# LED_driver.net
KiCad netlist of a schematic drawn in EAGLE
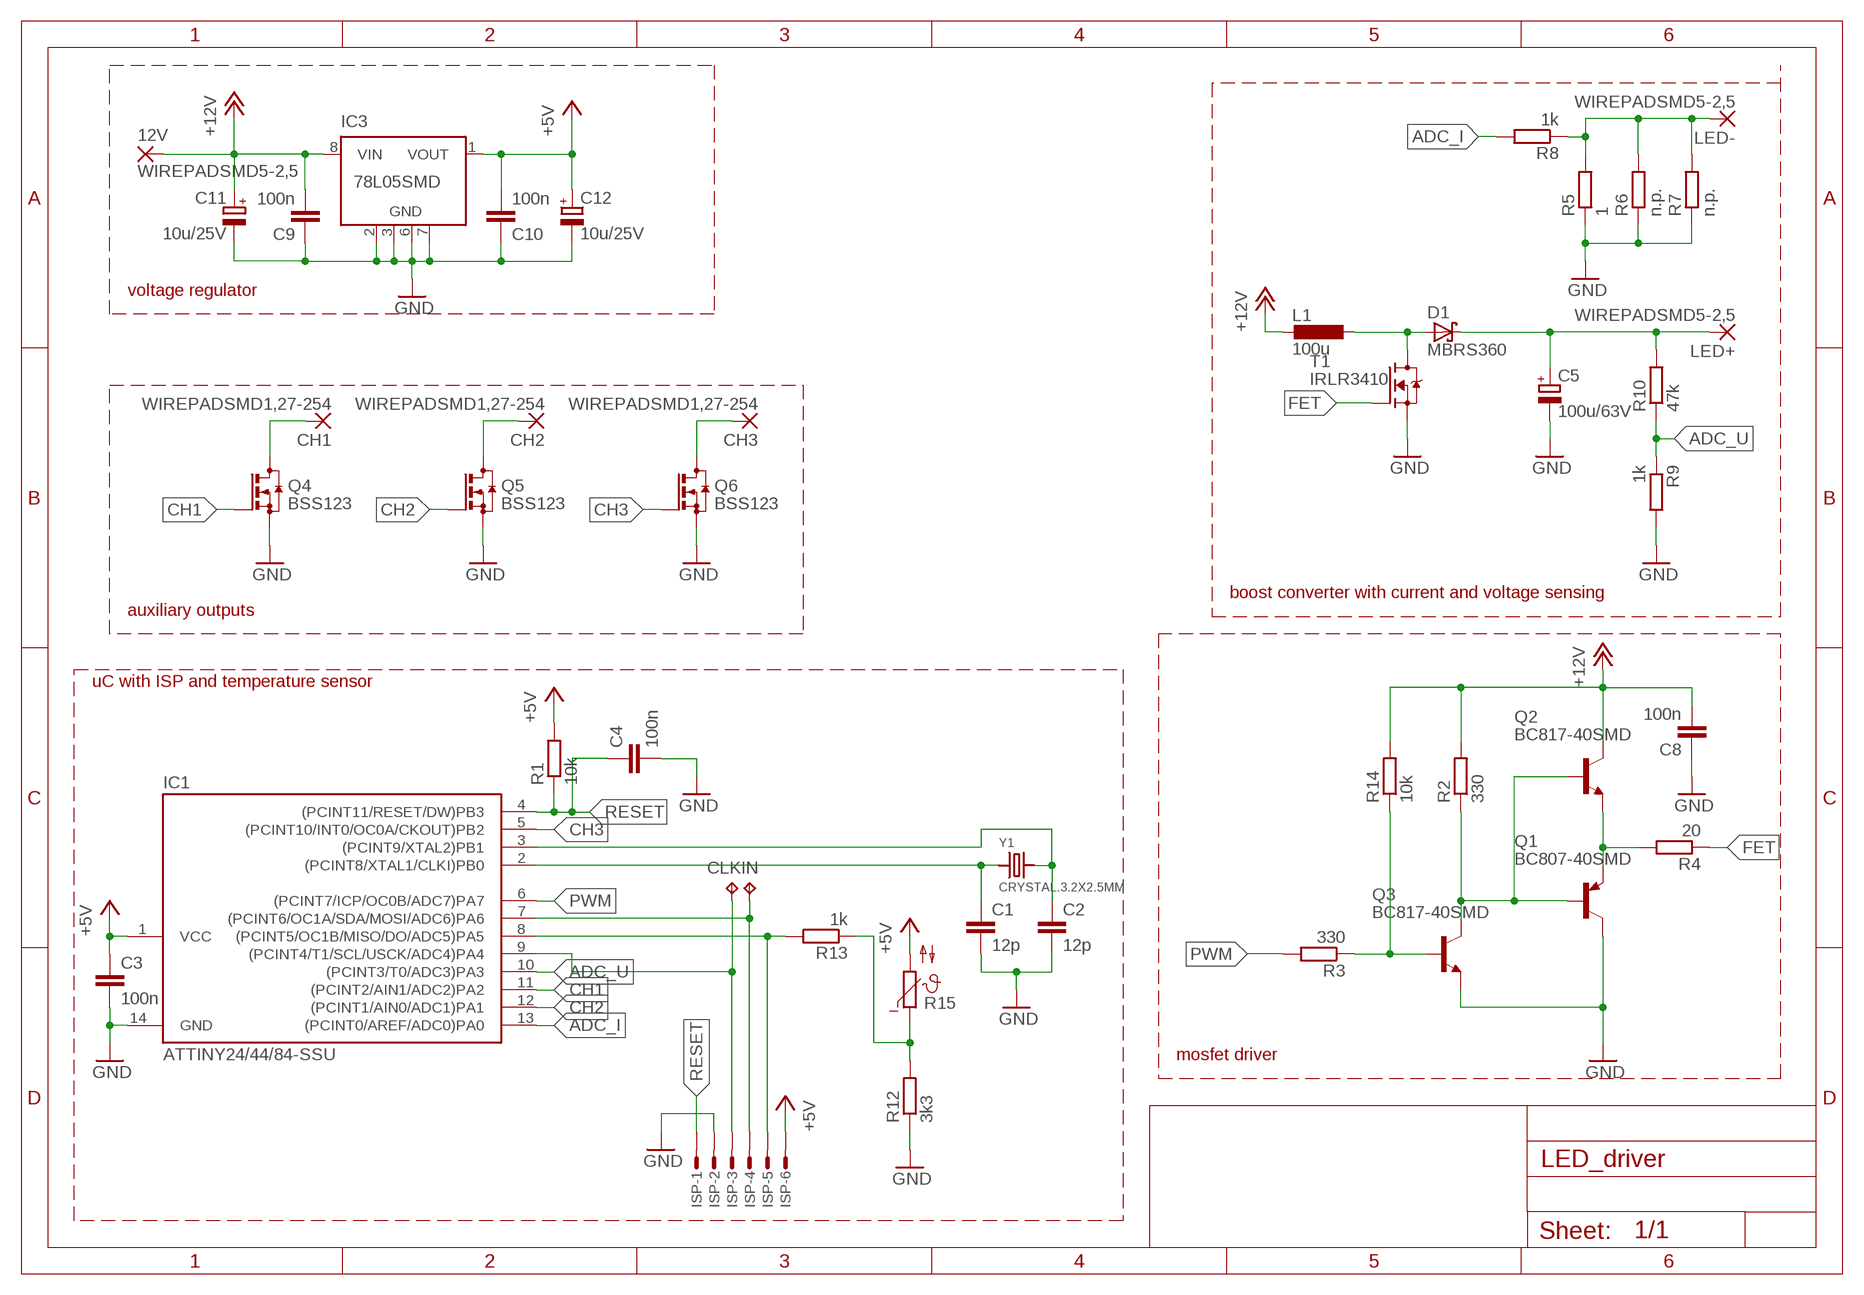
[diagram p0: schematic, sheet 1]

(export (version "E")
  (design (tool "Eeschema 10.0.6"))
  (components
    (comp (ref "12V")
      (value "WIREPADSMD5-2,5")
      (footprint "eagle-import:5-2,5")
      (libsource (lib "eagle-import") (part "WIREPADSMD5-2,5"))
    )
    (comp (ref "C1")
      (value "12p")
      (footprint "eagle-import:C0603K")
      (libsource (lib "eagle-import") (part "C-EUC0603K"))
    )
    (comp (ref "C2")
      (value "12p")
      (footprint "eagle-import:C0603K")
      (libsource (lib "eagle-import") (part "C-EUC0603K"))
    )
    (comp (ref "C3")
      (value "100n")
      (footprint "eagle-import:C0603K")
      (libsource (lib "eagle-import") (part "C-EUC0603K"))
    )
    (comp (ref "C4")
      (value "100n")
      (footprint "eagle-import:C0603K")
      (libsource (lib "eagle-import") (part "C-EUC0603K"))
    )
    (comp (ref "C5")
      (value "100u/63V")
      (footprint "eagle-import:153CLV-1010")
      (libsource (lib "eagle-import") (part "CPOL-EU153CLV-1010"))
    )
    (comp (ref "C8")
      (value "100n")
      (footprint "eagle-import:C0603K")
      (libsource (lib "eagle-import") (part "C-EUC0603K"))
    )
    (comp (ref "C9")
      (value "100n")
      (footprint "eagle-import:C0603K")
      (libsource (lib "eagle-import") (part "C-EUC0603K"))
    )
    (comp (ref "C10")
      (value "100n")
      (footprint "eagle-import:C0603K")
      (libsource (lib "eagle-import") (part "C-EUC0603K"))
    )
    (comp (ref "C11")
      (value "10u/25V")
      (footprint "eagle-import:153CLV-0405")
      (libsource (lib "eagle-import") (part "CPOL-EU153CLV-0405"))
    )
    (comp (ref "C12")
      (value "10u/25V")
      (footprint "eagle-import:153CLV-0405")
      (libsource (lib "eagle-import") (part "CPOL-EU153CLV-0405"))
    )
    (comp (ref "CH1")
      (value "WIREPADSMD1,27-254")
      (footprint "eagle-import:SMD1,27-2,54")
      (libsource (lib "eagle-import") (part "WIREPADSMD1,27-254"))
    )
    (comp (ref "CH2")
      (value "WIREPADSMD1,27-254")
      (footprint "eagle-import:SMD1,27-2,54")
      (libsource (lib "eagle-import") (part "WIREPADSMD1,27-254"))
    )
    (comp (ref "CH3")
      (value "WIREPADSMD1,27-254")
      (footprint "eagle-import:SMD1,27-2,54")
      (libsource (lib "eagle-import") (part "WIREPADSMD1,27-254"))
    )
    (comp (ref "CLK")
      (value "TPTP15R")
      (footprint "eagle-import:TP15R")
      (libsource (lib "eagle-import") (part "TPTP15R"))
    )
    (comp (ref "D1")
      (value "MBRS360")
      (footprint "eagle-import:SMC")
      (libsource (lib "eagle-import") (part "SCHOTTKY-DIODESMC"))
    )
    (comp (ref "IC1")
      (value "ATTINY24/44/84-SSU")
      (footprint "eagle-import:SOIC14")
      (libsource (lib "eagle-import") (part "ATTINY24/44/84-SSU"))
    )
    (comp (ref "IC3")
      (value "78L05SMD")
      (footprint "eagle-import:SO08")
      (libsource (lib "eagle-import") (part "78LSMD05"))
    )
    (comp (ref "IN")
      (value "TPTP15R")
      (footprint "eagle-import:TP15R")
      (libsource (lib "eagle-import") (part "TPTP15R"))
    )
    (comp (ref "ISP")
      (value "MICROMATCH-6SMF")
      (footprint "eagle-import:MMT-F-SMD-6")
      (libsource (lib "eagle-import") (part "MICROMATCH-6SMF"))
    )
    (comp (ref "L1")
      (value "100u")
      (footprint "eagle-import:PISM")
      (libsource (lib "eagle-import") (part "L-EUPISM"))
    )
    (comp (ref "LED+")
      (value "WIREPADSMD5-2,5")
      (footprint "eagle-import:5-2,5")
      (libsource (lib "eagle-import") (part "WIREPADSMD5-2,5"))
    )
    (comp (ref "LED-")
      (value "WIREPADSMD5-2,5")
      (footprint "eagle-import:5-2,5")
      (libsource (lib "eagle-import") (part "WIREPADSMD5-2,5"))
    )
    (comp (ref "Q1")
      (value "BC807-40SMD")
      (footprint "eagle-import:SOT23-BEC")
      (libsource (lib "eagle-import") (part "BC807SMD-40"))
    )
    (comp (ref "Q2")
      (value "BC817-40SMD")
      (footprint "eagle-import:SOT23-BEC")
      (libsource (lib "eagle-import") (part "BC817SMD-40"))
    )
    (comp (ref "Q3")
      (value "BC817-40SMD")
      (footprint "eagle-import:SOT23-BEC")
      (libsource (lib "eagle-import") (part "BC817SMD-40"))
    )
    (comp (ref "Q4")
      (value "BSS123")
      (footprint "eagle-import:SOT23")
      (libsource (lib "eagle-import") (part "BSS123"))
    )
    (comp (ref "Q5")
      (value "BSS123")
      (footprint "eagle-import:SOT23")
      (libsource (lib "eagle-import") (part "BSS123"))
    )
    (comp (ref "Q6")
      (value "BSS123")
      (footprint "eagle-import:SOT23")
      (libsource (lib "eagle-import") (part "BSS123"))
    )
    (comp (ref "R1")
      (value "10k")
      (footprint "eagle-import:R0603")
      (libsource (lib "eagle-import") (part "R-EU_R0603"))
    )
    (comp (ref "R2")
      (value "330")
      (footprint "eagle-import:R0603")
      (libsource (lib "eagle-import") (part "R-EU_R0603"))
    )
    (comp (ref "R3")
      (value "330")
      (footprint "eagle-import:R0603")
      (libsource (lib "eagle-import") (part "R-EU_R0603"))
    )
    (comp (ref "R4")
      (value "20")
      (footprint "eagle-import:R0603")
      (libsource (lib "eagle-import") (part "R-EU_R0603"))
    )
    (comp (ref "R5")
      (value "1")
      (footprint "eagle-import:R1206")
      (libsource (lib "eagle-import") (part "resistor_R-EU_R1206"))
    )
    (comp (ref "R6")
      (value "n.p.")
      (footprint "eagle-import:R1206")
      (libsource (lib "eagle-import") (part "resistor_R-EU_R1206"))
    )
    (comp (ref "R7")
      (value "n.p.")
      (footprint "eagle-import:R1206")
      (libsource (lib "eagle-import") (part "resistor_R-EU_R1206"))
    )
    (comp (ref "R8")
      (value "1k")
      (footprint "eagle-import:R0603")
      (libsource (lib "eagle-import") (part "R-EU_R0603"))
    )
    (comp (ref "R9")
      (value "1k")
      (footprint "eagle-import:R0603")
      (libsource (lib "eagle-import") (part "R-EU_R0603"))
    )
    (comp (ref "R10")
      (value "47k")
      (footprint "eagle-import:R0603")
      (libsource (lib "eagle-import") (part "R-EU_R0603"))
    )
    (comp (ref "R12")
      (value "3k3")
      (footprint "eagle-import:R0603")
      (libsource (lib "eagle-import") (part "R-EU_R0603"))
    )
    (comp (ref "R13")
      (value "1k")
      (footprint "eagle-import:R0603")
      (libsource (lib "eagle-import") (part "R-EU_R0603"))
    )
    (comp (ref "R14")
      (value "10k")
      (footprint "eagle-import:R0603")
      (libsource (lib "eagle-import") (part "R-EU_R0603"))
    )
    (comp (ref "R15")
      (value "NTC640")
      (footprint "eagle-import:P640")
      (libsource (lib "eagle-import") (part "NTC640"))
    )
    (comp (ref "T1")
      (value "IRLR3410")
      (footprint "eagle-import:TO252")
      (libsource (lib "eagle-import") (part "IRLR3410"))
    )
    (comp (ref "Y1")
      (value "CRYSTAL.3.2X2.5MM")
      (footprint "eagle-import:3.2X2.5MM")
      (libsource (lib "eagle-import") (part "CRYSTAL.3.2X2.5MM"))
    )
  )
  (nets
    (net (code "1") (name "+5V") (class "Default")
      (node (ref "C10") (pin "2") (pinfunction "2_2") (pintype "passive"))
      (node (ref "C12") (pin "+") (pinfunction "+_+") (pintype "passive"))
      (node (ref "C3") (pin "1") (pinfunction "1_1") (pintype "passive"))
      (node (ref "IC1") (pin "1") (pinfunction "VCC_1") (pintype "power_in"))
      (node (ref "IC3") (pin "1") (pinfunction "VOUT_1") (pintype "output"))
      (node (ref "ISP") (pin "6") (pinfunction "S_6") (pintype "passive"))
      (node (ref "R1") (pin "2") (pinfunction "2_2") (pintype "passive"))
      (node (ref "R15") (pin "2") (pinfunction "2_2") (pintype "passive"))
    )
    (net (code "2") (name "+12V") (class "Default")
      (node (ref "12V") (pin "1") (pinfunction "P_1") (pintype "passive"))
      (node (ref "C11") (pin "+") (pinfunction "+_+") (pintype "passive"))
      (node (ref "C8") (pin "2") (pinfunction "2_2") (pintype "passive"))
      (node (ref "C9") (pin "2") (pinfunction "2_2") (pintype "passive"))
      (node (ref "IC3") (pin "8") (pinfunction "VIN_8") (pintype "passive"))
      (node (ref "L1") (pin "2") (pinfunction "2_2") (pintype "passive"))
      (node (ref "Q2") (pin "C") (pinfunction "C_C") (pintype "passive"))
      (node (ref "R14") (pin "2") (pinfunction "2_2") (pintype "passive"))
      (node (ref "R2") (pin "2") (pinfunction "2_2") (pintype "passive"))
    )
    (net (code "3") (name "ADC_I") (class "Default")
      (node (ref "IC1") (pin "13") (pinfunction "(PCINT0/AREF/ADC0)PA0_13") (pintype "bidirectional"))
      (node (ref "R8") (pin "2") (pinfunction "2_2") (pintype "passive"))
    )
    (net (code "4") (name "ADC_U") (class "Default")
      (node (ref "IC1") (pin "10") (pinfunction "(PCINT3/T0/ADC3)PA3_10") (pintype "bidirectional"))
      (node (ref "R10") (pin "1") (pinfunction "1_1") (pintype "passive"))
      (node (ref "R9") (pin "1") (pinfunction "1_1") (pintype "passive"))
    )
    (net (code "5") (name "CH1") (class "Default")
      (node (ref "IC1") (pin "11") (pinfunction "(PCINT2/AIN1/ADC2)PA2_11") (pintype "bidirectional"))
      (node (ref "Q4") (pin "1") (pinfunction "G_1") (pintype "passive"))
    )
    (net (code "6") (name "CH2") (class "Default")
      (node (ref "IC1") (pin "12") (pinfunction "(PCINT1/AIN0/ADC1)PA1_12") (pintype "bidirectional"))
      (node (ref "Q5") (pin "1") (pinfunction "G_1") (pintype "passive"))
    )
    (net (code "7") (name "CH3") (class "Default")
      (node (ref "IC1") (pin "5") (pinfunction "(PCINT10/INT0/OC0A/CKOUT)PB2_5") (pintype "bidirectional"))
      (node (ref "Q6") (pin "1") (pinfunction "G_1") (pintype "passive"))
    )
    (net (code "8") (name "FET") (class "Default")
      (node (ref "R4") (pin "1") (pinfunction "1_1") (pintype "passive"))
      (node (ref "T1") (pin "1") (pinfunction "G_1") (pintype "passive"))
    )
    (net (code "9") (name "GND") (class "Default")
      (node (ref "C1") (pin "2") (pinfunction "2_2") (pintype "passive"))
      (node (ref "C10") (pin "1") (pinfunction "1_1") (pintype "passive"))
      (node (ref "C11") (pin "-") (pinfunction "-_-") (pintype "passive"))
      (node (ref "C12") (pin "-") (pinfunction "-_-") (pintype "passive"))
      (node (ref "C2") (pin "2") (pinfunction "2_2") (pintype "passive"))
      (node (ref "C3") (pin "2") (pinfunction "2_2") (pintype "passive"))
      (node (ref "C4") (pin "2") (pinfunction "2_2") (pintype "passive"))
      (node (ref "C5") (pin "-") (pinfunction "-_-") (pintype "passive"))
      (node (ref "C8") (pin "1") (pinfunction "1_1") (pintype "passive"))
      (node (ref "C9") (pin "1") (pinfunction "1_1") (pintype "passive"))
      (node (ref "IC1") (pin "14") (pinfunction "GND_14") (pintype "power_in"))
      (node (ref "IC3") (pin "2") (pinfunction "GND_2") (pintype "power_in"))
      (node (ref "IC3") (pin "3") (pinfunction "GND_3") (pintype "power_in"))
      (node (ref "IC3") (pin "6") (pinfunction "GND_6") (pintype "power_in"))
      (node (ref "IC3") (pin "7") (pinfunction "GND_7") (pintype "power_in"))
      (node (ref "ISP") (pin "2") (pinfunction "S_2") (pintype "passive"))
      (node (ref "Q1") (pin "C") (pinfunction "C_C") (pintype "passive"))
      (node (ref "Q3") (pin "E") (pinfunction "E_E") (pintype "passive"))
      (node (ref "Q4") (pin "2") (pinfunction "S_2") (pintype "passive"))
      (node (ref "Q5") (pin "2") (pinfunction "S_2") (pintype "passive"))
      (node (ref "Q6") (pin "2") (pinfunction "S_2") (pintype "passive"))
      (node (ref "R12") (pin "1") (pinfunction "1_1") (pintype "passive"))
      (node (ref "R5") (pin "1") (pinfunction "1_1") (pintype "passive"))
      (node (ref "R6") (pin "1") (pinfunction "1_1") (pintype "passive"))
      (node (ref "R7") (pin "1") (pinfunction "1_1") (pintype "passive"))
      (node (ref "R9") (pin "2") (pinfunction "2_2") (pintype "passive"))
      (node (ref "T1") (pin "2") (pinfunction "S_2") (pintype "passive"))
    )
    (net (code "10") (name "Net-(CH1-P)") (class "Default")
      (node (ref "CH1") (pin "1") (pinfunction "P_1") (pintype "passive"))
      (node (ref "Q4") (pin "3") (pinfunction "D_3") (pintype "passive"))
    )
    (net (code "11") (name "Net-(CH2-P)") (class "Default")
      (node (ref "CH2") (pin "1") (pinfunction "P_1") (pintype "passive"))
      (node (ref "Q5") (pin "3") (pinfunction "D_3") (pintype "passive"))
    )
    (net (code "12") (name "Net-(CH3-P)") (class "Default")
      (node (ref "CH3") (pin "1") (pinfunction "P_1") (pintype "passive"))
      (node (ref "Q6") (pin "3") (pinfunction "D_3") (pintype "passive"))
    )
    (net (code "13") (name "Net-(IC1-(PCINT4{slash}T1{slash}SCL{slash}USCK{slash}ADC4)PA4)") (class "Default")
      (node (ref "CLK") (pin "TP") (pinfunction "TP_TP") (pintype "input"))
      (node (ref "IC1") (pin "9") (pinfunction "(PCINT4/T1/SCL/USCK/ADC4)PA4_9") (pintype "bidirectional"))
      (node (ref "ISP") (pin "3") (pinfunction "S_3") (pintype "passive"))
    )
    (net (code "14") (name "Net-(IC1-(PCINT5{slash}OC1B{slash}MISO{slash}DO{slash}ADC5)PA5)") (class "Default")
      (node (ref "IC1") (pin "8") (pinfunction "(PCINT5/OC1B/MISO/DO/ADC5)PA5_8") (pintype "bidirectional"))
      (node (ref "ISP") (pin "5") (pinfunction "S_5") (pintype "passive"))
      (node (ref "R13") (pin "2") (pinfunction "2_2") (pintype "passive"))
    )
    (net (code "15") (name "Net-(IC1-(PCINT6{slash}OC1A{slash}SDA{slash}MOSI{slash}ADC6)PA6)") (class "Default")
      (node (ref "IC1") (pin "7") (pinfunction "(PCINT6/OC1A/SDA/MOSI/ADC6)PA6_7") (pintype "bidirectional"))
      (node (ref "IN") (pin "TP") (pinfunction "TP_TP") (pintype "input"))
      (node (ref "ISP") (pin "4") (pinfunction "S_4") (pintype "passive"))
    )
    (net (code "16") (name "Net-(IC1-(PCINT8{slash}XTAL1{slash}CLKI)PB0)") (class "Default")
      (node (ref "C1") (pin "1") (pinfunction "1_1") (pintype "passive"))
      (node (ref "IC1") (pin "2") (pinfunction "(PCINT8/XTAL1/CLKI)PB0_2") (pintype "bidirectional"))
      (node (ref "Y1") (pin "1") (pinfunction "1_1") (pintype "passive"))
    )
    (net (code "17") (name "Net-(IC1-(PCINT9{slash}XTAL2)PB1)") (class "Default")
      (node (ref "C2") (pin "1") (pinfunction "1_1") (pintype "passive"))
      (node (ref "IC1") (pin "3") (pinfunction "(PCINT9/XTAL2)PB1_3") (pintype "bidirectional"))
      (node (ref "Y1") (pin "3") (pinfunction "2_3") (pintype "passive"))
    )
    (net (code "18") (name "Net-(LED+-P)") (class "Default")
      (node (ref "C5") (pin "+") (pinfunction "+_+") (pintype "passive"))
      (node (ref "D1") (pin "C") (pinfunction "C_C") (pintype "passive"))
      (node (ref "LED+") (pin "1") (pinfunction "P_1") (pintype "passive"))
      (node (ref "R10") (pin "2") (pinfunction "2_2") (pintype "passive"))
    )
    (net (code "19") (name "Net-(LED--P)") (class "Default")
      (node (ref "LED-") (pin "1") (pinfunction "P_1") (pintype "passive"))
      (node (ref "R5") (pin "2") (pinfunction "2_2") (pintype "passive"))
      (node (ref "R6") (pin "2") (pinfunction "2_2") (pintype "passive"))
      (node (ref "R7") (pin "2") (pinfunction "2_2") (pintype "passive"))
      (node (ref "R8") (pin "1") (pinfunction "1_1") (pintype "passive"))
    )
    (net (code "20") (name "Net-(Q1-PadB)") (class "Default")
      (node (ref "Q1") (pin "B") (pinfunction "B_B") (pintype "passive"))
      (node (ref "Q2") (pin "B") (pinfunction "B_B") (pintype "passive"))
      (node (ref "Q3") (pin "C") (pinfunction "C_C") (pintype "passive"))
      (node (ref "R2") (pin "1") (pinfunction "1_1") (pintype "passive"))
    )
    (net (code "21") (name "Net-(Q1-PadE)") (class "Default")
      (node (ref "Q1") (pin "E") (pinfunction "E_E") (pintype "passive"))
      (node (ref "Q2") (pin "E") (pinfunction "E_E") (pintype "passive"))
      (node (ref "R4") (pin "2") (pinfunction "2_2") (pintype "passive"))
    )
    (net (code "22") (name "Net-(Q3-PadB)") (class "Default")
      (node (ref "Q3") (pin "B") (pinfunction "B_B") (pintype "passive"))
      (node (ref "R14") (pin "1") (pinfunction "1_1") (pintype "passive"))
      (node (ref "R3") (pin "1") (pinfunction "1_1") (pintype "passive"))
    )
    (net (code "23") (name "Net-(R12-Pad2)") (class "Default")
      (node (ref "R12") (pin "2") (pinfunction "2_2") (pintype "passive"))
      (node (ref "R13") (pin "1") (pinfunction "1_1") (pintype "passive"))
      (node (ref "R15") (pin "1") (pinfunction "1_1") (pintype "passive"))
    )
    (net (code "24") (name "Net-(T1-D)") (class "Default")
      (node (ref "D1") (pin "A") (pinfunction "A_A") (pintype "passive"))
      (node (ref "L1") (pin "1") (pinfunction "1_1") (pintype "passive"))
      (node (ref "T1") (pin "3") (pinfunction "D_3") (pintype "passive"))
    )
    (net (code "25") (name "PWM") (class "Default")
      (node (ref "IC1") (pin "6") (pinfunction "(PCINT7/ICP/OC0B/ADC7)PA7_6") (pintype "bidirectional"))
      (node (ref "R3") (pin "2") (pinfunction "2_2") (pintype "passive"))
    )
    (net (code "26") (name "RESET") (class "Default")
      (node (ref "C4") (pin "1") (pinfunction "1_1") (pintype "passive"))
      (node (ref "IC1") (pin "4") (pinfunction "(PCINT11/RESET/DW)PB3_4") (pintype "bidirectional"))
      (node (ref "ISP") (pin "1") (pinfunction "S_1") (pintype "passive"))
      (node (ref "R1") (pin "1") (pinfunction "1_1") (pintype "passive"))
    )
  )
)
